# poweramp_phase_splitter.net
KiCad netlist of a schematic drawn in Altium Designer
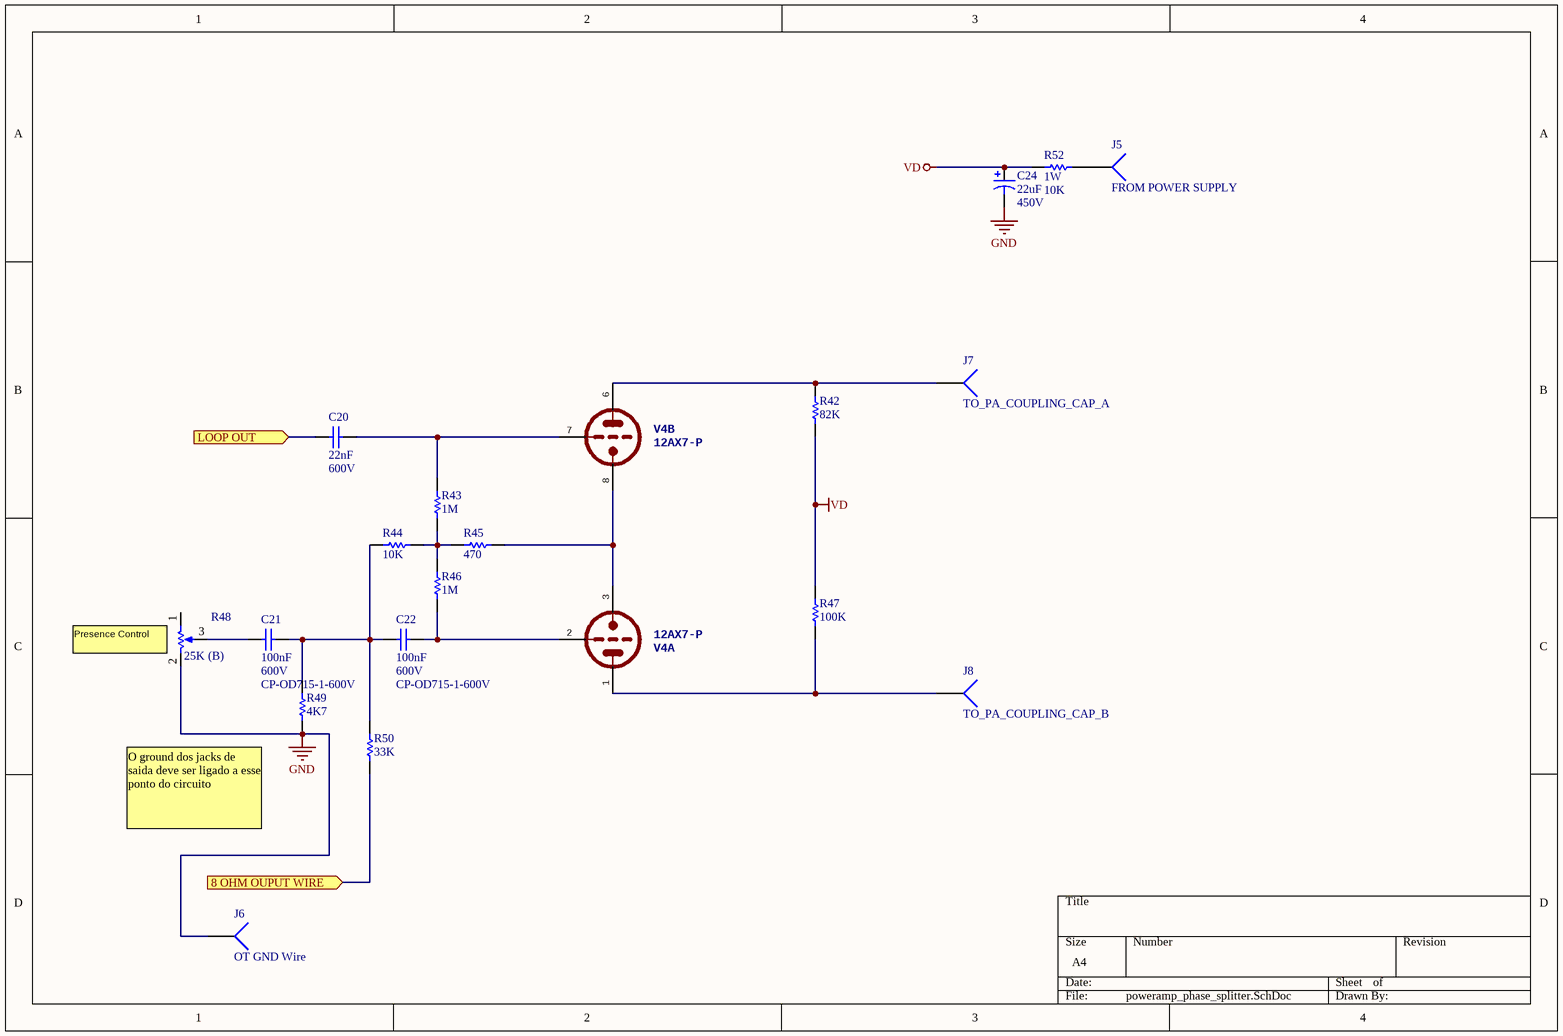
[diagram p0: poweramp_phase_splitter.SchDoc]

(export (version "E")
  (design (tool "Eeschema 10.0.6"))
  (components
    (comp (ref "C20")
      (value "22nF")
      (footprint "ORANGE-DROP-22nF-600V")
      (description "Capacitor")
      (fields
        (field (name "MANUFACTURERPARTNUMBER") "715P22356KD3")
        (field (name "VOLTAGE") "600V")
        (field (name "Comment") "Orange Drop Capacitor")
        (field (name "PUBLISHER") "Linda HB Amplifiers")
      )
      (libsource (lib "capacitors") (part "Cap-Orange-DROP-22nF-600V"))
    )
    (comp (ref "C21")
      (value "100nF")
      (footprint "ORANGE-DROP-100nF-600V")
      (description "Capacitor")
      (fields
        (field (name "MANUFACTURERPARTNUMBER") "715P10496L")
        (field (name "VOLTAGE") "600V")
        (field (name "TUBEDEPOT_SN") "CP-OD715-1-600V")
        (field (name "Comment") "Orange Drop Capacitor")
        (field (name "PUBLISHER") "Altium Limited")
      )
      (libsource (lib "capacitors") (part "Cap-Orange-DROP-100nF-600V"))
    )
    (comp (ref "C22")
      (value "100nF")
      (footprint "ORANGE-DROP-100nF-600V")
      (description "Capacitor")
      (fields
        (field (name "MANUFACTURERPARTNUMBER") "715P10496L")
        (field (name "VOLTAGE") "600V")
        (field (name "TUBEDEPOT_SN") "CP-OD715-1-600V")
        (field (name "Comment") "Orange Drop Capacitor")
        (field (name "PUBLISHER") "Altium Limited")
      )
      (libsource (lib "capacitors") (part "Cap-Orange-DROP-100nF-600V"))
    )
    (comp (ref "C24")
      (value "22uF")
      (footprint "RAD-POL-7.6-15")
      (description "Polarized Capacitor (Axial)")
      (fields
        (field (name "VOLTAGE") "450V")
        (field (name "Comment") "Cap Pol Rad")
        (field (name "PUBLISHER") "Altium Limited")
      )
      (libsource (lib "capacitors") (part "Cap Pol Rad"))
    )
    (comp (ref "J5")
      (value "FROM POWER SUPPLY")
      (footprint "PIN1")
      (description "Socket")
      (fields (field (name "PUBLISHER") "Altium Limited"))
      (libsource (lib "Miscellaneous Connectors") (part "Socket"))
    )
    (comp (ref "J6")
      (value "OT GND Wire")
      (footprint "PIN1")
      (description "FromOTGroundWire")
      (fields (field (name "PUBLISHER") "Altium Limited"))
      (libsource (lib "Miscellaneous Connectors") (part "Socket"))
    )
    (comp (ref "J7")
      (value "TO_PA_COUPLING_CAP_A")
      (footprint "PIN1")
      (description "Socket")
      (fields (field (name "PUBLISHER") "Altium Limited"))
      (libsource (lib "Miscellaneous Connectors") (part "Socket"))
    )
    (comp (ref "J8")
      (value "TO_PA_COUPLING_CAP_B")
      (footprint "PIN1")
      (description "Socket")
      (fields (field (name "PUBLISHER") "Altium Limited"))
      (libsource (lib "Miscellaneous Connectors") (part "Socket"))
    )
    (comp (ref "R42")
      (value "82K")
      (footprint "AXIAL-0.6")
      (description "Semiconductor Resistor")
      (fields
        (field (name "POWER") "1/2W")
        (field (name "Comment") "Metal Film Resistor 1/2W")
        (field (name "PUBLISHER") "Whitesheep Amps")
      )
      (libsource (lib "resistors") (part "Res Metal Film 1/2W"))
    )
    (comp (ref "R43")
      (value "1M")
      (footprint "AXIAL-0.6")
      (description "Semiconductor Resistor")
      (fields
        (field (name "POWER") "1/2W")
        (field (name "Comment") "Metal Film Resistor 1/2W")
        (field (name "PUBLISHER") "Whitesheep Amps")
      )
      (libsource (lib "resistors") (part "Res Metal Film 1/2W"))
    )
    (comp (ref "R44")
      (value "10K")
      (footprint "AXIAL-0.6")
      (description "Semiconductor Resistor")
      (fields
        (field (name "POWER") "1/2W")
        (field (name "Comment") "Metal Film Resistor 1/2W")
        (field (name "PUBLISHER") "Whitesheep Amps")
      )
      (libsource (lib "resistors") (part "Res Metal Film 1/2W"))
    )
    (comp (ref "R45")
      (value "470")
      (footprint "AXIAL-0.6")
      (description "Semiconductor Resistor")
      (fields
        (field (name "POWER") "1/2W")
        (field (name "Comment") "Metal Film Resistor 1/2W")
        (field (name "PUBLISHER") "Whitesheep Amps")
      )
      (libsource (lib "resistors") (part "Res Metal Film 1/2W"))
    )
    (comp (ref "R46")
      (value "1M")
      (footprint "AXIAL-0.6")
      (description "Semiconductor Resistor")
      (fields
        (field (name "POWER") "1/2W")
        (field (name "Comment") "Metal Film Resistor 1/2W")
        (field (name "PUBLISHER") "Whitesheep Amps")
      )
      (libsource (lib "resistors") (part "Res Metal Film 1/2W"))
    )
    (comp (ref "R47")
      (value "100K")
      (footprint "AXIAL-0.6")
      (description "Semiconductor Resistor")
      (fields
        (field (name "POWER") "1/2W")
        (field (name "Comment") "Metal Film Resistor 1/2W")
        (field (name "PUBLISHER") "Whitesheep Amps")
      )
      (libsource (lib "resistors") (part "Res Metal Film 1/2W"))
    )
    (comp (ref "R48")
      (value "25K")
      (footprint "pot_alpha - 2.54mm")
      (description "Potentiometer")
      (fields
        (field (name "TYPE") "(B)")
        (field (name "Comment") "ALPHA Potentiometer")
        (field (name "PUBLISHER") "Altium Limited")
      )
      (libsource (lib "potentiometers") (part "alpha-pot"))
    )
    (comp (ref "R49")
      (value "4K7")
      (footprint "AXIAL-0.6")
      (description "Semiconductor Resistor")
      (fields
        (field (name "POWER") "1/2W")
        (field (name "Comment") "Metal Film Resistor 1/2W")
        (field (name "PUBLISHER") "Whitesheep Amps")
      )
      (libsource (lib "resistors") (part "Res Metal Film 1/2W"))
    )
    (comp (ref "R50")
      (value "33K")
      (footprint "AXIAL-0.6")
      (description "Semiconductor Resistor")
      (fields
        (field (name "POWER") "1/2W")
        (field (name "Comment") "Metal Film Resistor 1/2W")
        (field (name "PUBLISHER") "Whitesheep Amps")
      )
      (libsource (lib "resistors") (part "Res Metal Film 1/2W"))
    )
    (comp (ref "R52")
      (value "10K")
      (footprint "AXIAL-0.6")
      (description "Semiconductor Resistor")
      (fields
        (field (name "POWER") "1W")
        (field (name "Comment") "Metal Film Resistor 1W")
        (field (name "PUBLISHER") "Linda Hand Buit Amplifiers")
      )
      (libsource (lib "resistors") (part "Res Wire Wound 1W"))
    )
    (comp (ref "V4")
      (value "12AX7-P")
      (footprint "NOVAL")
      (libsource (lib "eagle_tubes_v6") (part "12AX7-P"))
    )
  )
  (nets
    (net (code "1") (name "/8 OHM OUPUT WIRE") (class "Default")
      (node (ref "R50") (pin "1") (pinfunction "1_1") (pintype "passive"))
    )
    (net (code "2") (name "/LOOP OUT") (class "Default")
      (node (ref "C20") (pin "1") (pinfunction "1_1") (pintype "passive"))
    )
    (net (code "3") (name "GND") (class "Default")
      (node (ref "C24") (pin "2") (pinfunction "2_2") (pintype "passive"))
      (node (ref "J6") (pin "1") (pinfunction "1_1") (pintype "passive"))
      (node (ref "R48") (pin "2") (pinfunction "BOT_2") (pintype "passive"))
      (node (ref "R49") (pin "1") (pinfunction "1_1") (pintype "passive"))
    )
    (net (code "4") (name "Net-(C21-Pad2)") (class "Default")
      (node (ref "C21") (pin "2") (pinfunction "2_2") (pintype "passive"))
      (node (ref "C22") (pin "1") (pinfunction "1_1") (pintype "passive"))
      (node (ref "R44") (pin "2") (pinfunction "2_2") (pintype "passive"))
      (node (ref "R49") (pin "2") (pinfunction "2_2") (pintype "passive"))
      (node (ref "R50") (pin "2") (pinfunction "2_2") (pintype "passive"))
    )
    (net (code "5") (name "Net-(J5-Pad1)") (class "Default")
      (node (ref "J5") (pin "1") (pinfunction "1_1") (pintype "passive"))
      (node (ref "R52") (pin "1") (pinfunction "1_1") (pintype "passive"))
    )
    (net (code "6") (name "Net-(R43-Pad2)") (class "Default")
      (node (ref "R43") (pin "2") (pinfunction "2_2") (pintype "passive"))
      (node (ref "R44") (pin "1") (pinfunction "1_1") (pintype "passive"))
      (node (ref "R45") (pin "2") (pinfunction "2_2") (pintype "passive"))
      (node (ref "R46") (pin "1") (pinfunction "1_1") (pintype "passive"))
    )
    (net (code "7") (name "Net-(R48-TAP)") (class "Default")
      (node (ref "C21") (pin "1") (pinfunction "1_1") (pintype "passive"))
      (node (ref "R48") (pin "3") (pinfunction "TAP_3") (pintype "passive"))
    )
    (net (code "8") (name "Net-(V4A-TA)") (class "Default")
      (node (ref "J8") (pin "1") (pinfunction "1_1") (pintype "passive"))
      (node (ref "R47") (pin "2") (pinfunction "2_2") (pintype "passive"))
      (node (ref "V4") (pin "1") (pinfunction "TA_1") (pintype "passive"))
    )
    (net (code "9") (name "Net-(V4A-TG)") (class "Default")
      (node (ref "C22") (pin "2") (pinfunction "2_2") (pintype "passive"))
      (node (ref "R46") (pin "2") (pinfunction "2_2") (pintype "passive"))
      (node (ref "V4") (pin "2") (pinfunction "TG_2") (pintype "passive"))
    )
    (net (code "10") (name "Net-(V4A-TK)") (class "Default")
      (node (ref "R45") (pin "1") (pinfunction "1_1") (pintype "passive"))
      (node (ref "V4") (pin "3") (pinfunction "TK_3") (pintype "passive"))
      (node (ref "V4") (pin "8") (pinfunction "TK_8") (pintype "passive"))
    )
    (net (code "11") (name "Net-(V4B-TA)") (class "Default")
      (node (ref "J7") (pin "1") (pinfunction "1_1") (pintype "passive"))
      (node (ref "R42") (pin "1") (pinfunction "1_1") (pintype "passive"))
      (node (ref "V4") (pin "6") (pinfunction "TA_6") (pintype "passive"))
    )
    (net (code "12") (name "Net-(V4B-TG)") (class "Default")
      (node (ref "C20") (pin "2") (pinfunction "2_2") (pintype "passive"))
      (node (ref "R43") (pin "1") (pinfunction "1_1") (pintype "passive"))
      (node (ref "V4") (pin "7") (pinfunction "TG_7") (pintype "passive"))
    )
    (net (code "13") (name "VD") (class "Default")
      (node (ref "C24") (pin "1") (pinfunction "1_1") (pintype "passive"))
      (node (ref "R42") (pin "2") (pinfunction "2_2") (pintype "passive"))
      (node (ref "R47") (pin "1") (pinfunction "1_1") (pintype "passive"))
      (node (ref "R52") (pin "2") (pinfunction "2_2") (pintype "passive"))
    )
    (net (code "14") (name "unconnected-(R48-TOP-Pad1)") (class "Default")
      (node (ref "R48") (pin "1") (pinfunction "TOP_1") (pintype "passive"))
    )
  )
)
